# Driver_Filter.net
KiCad netlist of a schematic drawn in Altium Designer
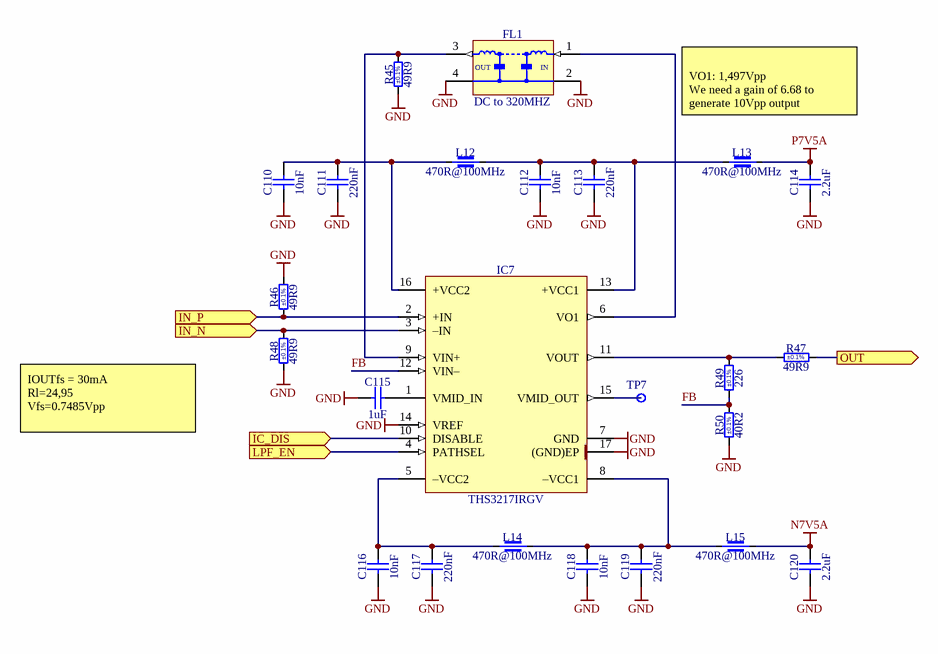
[diagram p0: Driver_Filter.schdoc]

(export (version "E")
  (design (tool "Eeschema 10.0.6"))
  (components
    (comp (ref "C110")
      (value "10nF")
      (footprint "CAPC1005X55N")
      (description "Non-polarised capacitor")
      (fields
        (field (name "PART NUMBER") "CC0402_10NF_16V_10%_X7R")
        (field (name "VOLTAGE") "16V")
        (field (name "AUTHOR") "CERN DEM JLC")
      )
      (libsource (lib "Capacitors") (part "Capacitor - non polarized"))
    )
    (comp (ref "C111")
      (value "220nF")
      (footprint "CAPC1005X55N")
      (description "Non-polarised capacitor")
      (fields
        (field (name "PART NUMBER") "CC0402_220NF_16V_10%_X7R")
        (field (name "VOLTAGE") "16V")
        (field (name "AUTHOR") "CERN DEM JLC")
      )
      (libsource (lib "Capacitors") (part "Capacitor - non polarized"))
    )
    (comp (ref "C112")
      (value "10nF")
      (footprint "CAPC1005X55N")
      (description "Non-polarised capacitor")
      (fields
        (field (name "PART NUMBER") "CC0402_10NF_16V_10%_X7R")
        (field (name "VOLTAGE") "16V")
        (field (name "AUTHOR") "CERN DEM JLC")
      )
      (libsource (lib "Capacitors") (part "Capacitor - non polarized"))
    )
    (comp (ref "C113")
      (value "220nF")
      (footprint "CAPC1005X55N")
      (description "Non-polarised capacitor")
      (fields
        (field (name "PART NUMBER") "CC0402_220NF_16V_10%_X7R")
        (field (name "VOLTAGE") "16V")
        (field (name "AUTHOR") "CERN DEM JLC")
      )
      (libsource (lib "Capacitors") (part "Capacitor - non polarized"))
    )
    (comp (ref "C114")
      (value "2.2uF")
      (footprint "CAPC1005X55N")
      (description "Non-polarised capacitor")
      (fields
        (field (name "PART NUMBER") "CC0402_2.2UF_16V_10%_X5R")
        (field (name "VOLTAGE") "16V")
        (field (name "AUTHOR") "CERN DEM BC")
      )
      (libsource (lib "Capacitors") (part "Capacitor - non polarized"))
    )
    (comp (ref "C115")
      (value "1uF")
      (footprint "CAPC1005X55N")
      (description "Non-polarised capacitor")
      (fields
        (field (name "PART NUMBER") "CC0402_1UF_16V_10%_X5R")
        (field (name "VOLTAGE") "16V")
        (field (name "AUTHOR") "CERN DEM JLC")
      )
      (libsource (lib "Capacitors") (part "Capacitor - non polarized"))
    )
    (comp (ref "C116")
      (value "10nF")
      (footprint "CAPC1005X55N")
      (description "Non-polarised capacitor")
      (fields
        (field (name "PART NUMBER") "CC0402_10NF_16V_10%_X7R")
        (field (name "VOLTAGE") "16V")
        (field (name "AUTHOR") "CERN DEM JLC")
      )
      (libsource (lib "Capacitors") (part "Capacitor - non polarized"))
    )
    (comp (ref "C117")
      (value "220nF")
      (footprint "CAPC1005X55N")
      (description "Non-polarised capacitor")
      (fields
        (field (name "PART NUMBER") "CC0402_220NF_16V_10%_X7R")
        (field (name "VOLTAGE") "16V")
        (field (name "AUTHOR") "CERN DEM JLC")
      )
      (libsource (lib "Capacitors") (part "Capacitor - non polarized"))
    )
    (comp (ref "C118")
      (value "10nF")
      (footprint "CAPC1005X55N")
      (description "Non-polarised capacitor")
      (fields
        (field (name "PART NUMBER") "CC0402_10NF_16V_10%_X7R")
        (field (name "VOLTAGE") "16V")
        (field (name "AUTHOR") "CERN DEM JLC")
      )
      (libsource (lib "Capacitors") (part "Capacitor - non polarized"))
    )
    (comp (ref "C119")
      (value "220nF")
      (footprint "CAPC1005X55N")
      (description "Non-polarised capacitor")
      (fields
        (field (name "PART NUMBER") "CC0402_220NF_16V_10%_X7R")
        (field (name "VOLTAGE") "16V")
        (field (name "AUTHOR") "CERN DEM JLC")
      )
      (libsource (lib "Capacitors") (part "Capacitor - non polarized"))
    )
    (comp (ref "C120")
      (value "2.2uF")
      (footprint "CAPC1005X55N")
      (description "Non-polarised capacitor")
      (fields
        (field (name "PART NUMBER") "CC0402_2.2UF_16V_10%_X5R")
        (field (name "VOLTAGE") "16V")
        (field (name "AUTHOR") "CERN DEM BC")
      )
      (libsource (lib "Capacitors") (part "Capacitor - non polarized"))
    )
    (comp (ref "FL1")
      (value "DC to 320MHZ")
      (footprint "FIL_MINI-CIRCUITS_FV1206")
      (description "50 Ohm Low Pass Filter")
      (fields
        (field (name "PART NUMBER") "FIL_MINI-CIRCUITS_LFCN-320+")
        (field (name "MANUFACTURER") "MINI-CIRCUITS")
        (field (name "AUTHOR") "CERN DEM MR")
      )
      (libsource (lib "Inductors & Transformers") (part "FIL_MINI-CIRCUITS_LFCN"))
    )
    (comp (ref "IC7")
      (value "THS3217IRGV")
      (footprint "QFN65P400X400X100-17N-S225")
      (description "DC to 800-MHz, Differential-to-Single-Ended, DAC Output Amplifier")
      (fields (field (name "MANUFACTURER") "TEXAS INSTRUMENTS") (field (name "AUTHOR") "CERN DEM HF"))
      (libsource (lib "ICs And Semiconductors") (part "THS3217"))
    )
    (comp (ref "L12")
      (value "470R@100MHz")
      (footprint "INDC1608X95N")
      (fields
        (field (name "PART NUMBER") "IND0603_MURATA_BLM18PG471SN1D")
        (field (name "POWER") "1A")
        (field (name "TOLERANCE") "±25%")
        (field (name "AUTHOR") "CERN DEM BC")
      )
      (libsource (lib "Inductors & Transformers") (part "Ferrite Bead"))
    )
    (comp (ref "L13")
      (value "470R@100MHz")
      (footprint "INDC1608X95N")
      (fields
        (field (name "PART NUMBER") "IND0603_MURATA_BLM18PG471SN1D")
        (field (name "POWER") "1A")
        (field (name "TOLERANCE") "±25%")
        (field (name "AUTHOR") "CERN DEM BC")
      )
      (libsource (lib "Inductors & Transformers") (part "Ferrite Bead"))
    )
    (comp (ref "L14")
      (value "470R@100MHz")
      (footprint "INDC1608X95N")
      (fields
        (field (name "PART NUMBER") "IND0603_MURATA_BLM18PG471SN1D")
        (field (name "POWER") "1A")
        (field (name "TOLERANCE") "±25%")
        (field (name "AUTHOR") "CERN DEM BC")
      )
      (libsource (lib "Inductors & Transformers") (part "Ferrite Bead"))
    )
    (comp (ref "L15")
      (value "470R@100MHz")
      (footprint "INDC1608X95N")
      (fields
        (field (name "PART NUMBER") "IND0603_MURATA_BLM18PG471SN1D")
        (field (name "POWER") "1A")
        (field (name "TOLERANCE") "±25%")
        (field (name "AUTHOR") "CERN DEM BC")
      )
      (libsource (lib "Inductors & Transformers") (part "Ferrite Bead"))
    )
    (comp (ref "R45")
      (value "49R9")
      (footprint "RESC1608X55N")
      (description "Resistor - 0.1%")
      (fields
        (field (name "TOLERANCE") "±0.1%")
        (field (name "PART NUMBER") "R0603_49R9_0.1%_0.063W_10PPM")
        (field (name "POWER") "0.063W")
        (field (name "AUTHOR") "CERN DEM JLC")
      )
      (libsource (lib "Resistors") (part "Resistor - 0.1%"))
    )
    (comp (ref "R46")
      (value "49R9")
      (footprint "RESC1608X55N")
      (description "Resistor - 0.1%")
      (fields
        (field (name "TOLERANCE") "±0.1%")
        (field (name "PART NUMBER") "R0603_49R9_0.1%_0.063W_10PPM")
        (field (name "POWER") "0.063W")
        (field (name "AUTHOR") "CERN DEM JLC")
      )
      (libsource (lib "Resistors") (part "Resistor - 0.1%"))
    )
    (comp (ref "R47")
      (value "49R9")
      (footprint "RESC1608X55N")
      (description "Resistor - 0.1%")
      (fields
        (field (name "TOLERANCE") "±0.1%")
        (field (name "PART NUMBER") "R0603_49R9_0.1%_0.063W_10PPM")
        (field (name "POWER") "0.063W")
        (field (name "AUTHOR") "CERN DEM JLC")
      )
      (libsource (lib "Resistors") (part "Resistor - 0.1%"))
    )
    (comp (ref "R48")
      (value "49R9")
      (footprint "RESC1608X55N")
      (description "Resistor - 0.1%")
      (fields
        (field (name "TOLERANCE") "±0.1%")
        (field (name "PART NUMBER") "R0603_49R9_0.1%_0.063W_10PPM")
        (field (name "POWER") "0.063W")
        (field (name "AUTHOR") "CERN DEM JLC")
      )
      (libsource (lib "Resistors") (part "Resistor - 0.1%"))
    )
    (comp (ref "R49")
      (value "226")
      (footprint "RESC1608X55N")
      (description "Resistor - 0.1%")
      (fields
        (field (name "TOLERANCE") "±0.1%")
        (field (name "PART NUMBER") "R0603_226R_0.1%_0.063W_10PPM")
        (field (name "POWER") "0.063W")
        (field (name "AUTHOR") "CERN DEM JLC")
      )
      (libsource (lib "Resistors") (part "Resistor - 0.1%"))
    )
    (comp (ref "R50")
      (value "40R2")
      (footprint "RESC1608X55N")
      (description "Resistor - 0.1%")
      (fields
        (field (name "TOLERANCE") "±0.1%")
        (field (name "PART NUMBER") "R0603_40R2_0.1%_0.063W_10PPM")
        (field (name "POWER") "0.063W")
        (field (name "AUTHOR") "CERN DEM JLC")
      )
      (libsource (lib "Resistors") (part "Resistor - 0.1%"))
    )
    (comp (ref "TP7")
      (value "Test Point")
      (footprint "TPS127")
      (fields (field (name "PART NUMBER") "SMD_PAD_1.27X1.27MM") (field (name "AUTHOR") "CERN DEM JLC"))
      (libsource (lib "Eletro-mechanical") (part "Test Point"))
    )
  )
  (nets
    (net (code "1") (name "/FB") (class "Default")
      (node (ref "IC7") (pin "12") (pinfunction "VIN–_12") (pintype "input"))
      (node (ref "R49") (pin "1") (pinfunction "1_1") (pintype "passive"))
      (node (ref "R50") (pin "2") (pinfunction "2_2") (pintype "passive"))
    )
    (net (code "2") (name "/IC_DIS") (class "Default")
      (node (ref "IC7") (pin "10") (pinfunction "DISABLE_10") (pintype "input"))
    )
    (net (code "3") (name "/IN_N") (class "Default")
      (node (ref "IC7") (pin "3") (pinfunction "–IN_3") (pintype "input"))
      (node (ref "R48") (pin "2") (pinfunction "2_2") (pintype "passive"))
    )
    (net (code "4") (name "/IN_P") (class "Default")
      (node (ref "IC7") (pin "2") (pinfunction "+IN_2") (pintype "input"))
      (node (ref "R46") (pin "1") (pinfunction "1_1") (pintype "passive"))
    )
    (net (code "5") (name "/LPF_EN") (class "Default")
      (node (ref "IC7") (pin "4") (pinfunction "PATHSEL_4") (pintype "input"))
    )
    (net (code "6") (name "/OUT") (class "Default")
      (node (ref "R47") (pin "2") (pinfunction "2_2") (pintype "passive"))
    )
    (net (code "7") (name "GND") (class "Default")
      (node (ref "C110") (pin "1") (pinfunction "1_1") (pintype "passive"))
      (node (ref "C111") (pin "1") (pinfunction "1_1") (pintype "passive"))
      (node (ref "C112") (pin "1") (pinfunction "1_1") (pintype "passive"))
      (node (ref "C113") (pin "1") (pinfunction "1_1") (pintype "passive"))
      (node (ref "C114") (pin "1") (pinfunction "1_1") (pintype "passive"))
      (node (ref "C115") (pin "1") (pinfunction "1_1") (pintype "passive"))
      (node (ref "C116") (pin "1") (pinfunction "1_1") (pintype "passive"))
      (node (ref "C117") (pin "1") (pinfunction "1_1") (pintype "passive"))
      (node (ref "C118") (pin "1") (pinfunction "1_1") (pintype "passive"))
      (node (ref "C119") (pin "1") (pinfunction "1_1") (pintype "passive"))
      (node (ref "C120") (pin "1") (pinfunction "1_1") (pintype "passive"))
      (node (ref "FL1") (pin "2") (pinfunction "GND_2") (pintype "power_in"))
      (node (ref "FL1") (pin "4") (pinfunction "GND_4") (pintype "power_in"))
      (node (ref "IC7") (pin "14") (pinfunction "VREF_14") (pintype "input"))
      (node (ref "IC7") (pin "17") (pinfunction "(GND)EP_17") (pintype "power_in"))
      (node (ref "IC7") (pin "7") (pinfunction "GND_7") (pintype "power_in"))
      (node (ref "R45") (pin "1") (pinfunction "1_1") (pintype "passive"))
      (node (ref "R46") (pin "2") (pinfunction "2_2") (pintype "passive"))
      (node (ref "R48") (pin "1") (pinfunction "1_1") (pintype "passive"))
      (node (ref "R50") (pin "1") (pinfunction "1_1") (pintype "passive"))
    )
    (net (code "8") (name "N7V5A") (class "Default")
      (node (ref "C120") (pin "2") (pinfunction "2_2") (pintype "passive"))
      (node (ref "L15") (pin "2") (pinfunction "2_2") (pintype "passive"))
    )
    (net (code "9") (name "Net-(FL1-RFIN)") (class "Default")
      (node (ref "FL1") (pin "1") (pinfunction "RFIN_1") (pintype "input"))
      (node (ref "IC7") (pin "6") (pinfunction "VO1_6") (pintype "output"))
    )
    (net (code "10") (name "Net-(FL1-RFOUT)") (class "Default")
      (node (ref "FL1") (pin "3") (pinfunction "RFOUT_3") (pintype "output"))
      (node (ref "IC7") (pin "9") (pinfunction "VIN+_9") (pintype "input"))
      (node (ref "R45") (pin "2") (pinfunction "2_2") (pintype "passive"))
    )
    (net (code "11") (name "Net-(IC7-+VCC1)") (class "Default")
      (node (ref "C112") (pin "2") (pinfunction "2_2") (pintype "passive"))
      (node (ref "C113") (pin "2") (pinfunction "2_2") (pintype "passive"))
      (node (ref "IC7") (pin "13") (pinfunction "+VCC1_13") (pintype "power_in"))
      (node (ref "L12") (pin "2") (pinfunction "2_2") (pintype "passive"))
      (node (ref "L13") (pin "1") (pinfunction "1_1") (pintype "passive"))
    )
    (net (code "12") (name "Net-(IC7-+VCC2)") (class "Default")
      (node (ref "C110") (pin "2") (pinfunction "2_2") (pintype "passive"))
      (node (ref "C111") (pin "2") (pinfunction "2_2") (pintype "passive"))
      (node (ref "IC7") (pin "16") (pinfunction "+VCC2_16") (pintype "power_in"))
      (node (ref "L12") (pin "1") (pinfunction "1_1") (pintype "passive"))
    )
    (net (code "13") (name "Net-(IC7-VMID_IN)") (class "Default")
      (node (ref "C115") (pin "2") (pinfunction "2_2") (pintype "passive"))
      (node (ref "IC7") (pin "1") (pinfunction "VMID_IN_1") (pintype "power_in"))
    )
    (net (code "14") (name "Net-(IC7-VMID_OUT)") (class "Default")
      (node (ref "IC7") (pin "15") (pinfunction "VMID_OUT_15") (pintype "output"))
      (node (ref "TP7") (pin "1") (pinfunction "1_1") (pintype "bidirectional"))
    )
    (net (code "15") (name "Net-(IC7-VOUT)") (class "Default")
      (node (ref "IC7") (pin "11") (pinfunction "VOUT_11") (pintype "output"))
      (node (ref "R47") (pin "1") (pinfunction "1_1") (pintype "passive"))
      (node (ref "R49") (pin "2") (pinfunction "2_2") (pintype "passive"))
    )
    (net (code "16") (name "Net-(IC7-–VCC1)") (class "Default")
      (node (ref "C118") (pin "2") (pinfunction "2_2") (pintype "passive"))
      (node (ref "C119") (pin "2") (pinfunction "2_2") (pintype "passive"))
      (node (ref "IC7") (pin "8") (pinfunction "–VCC1_8") (pintype "power_in"))
      (node (ref "L14") (pin "2") (pinfunction "2_2") (pintype "passive"))
      (node (ref "L15") (pin "1") (pinfunction "1_1") (pintype "passive"))
    )
    (net (code "17") (name "Net-(IC7-–VCC2)") (class "Default")
      (node (ref "C116") (pin "2") (pinfunction "2_2") (pintype "passive"))
      (node (ref "C117") (pin "2") (pinfunction "2_2") (pintype "passive"))
      (node (ref "IC7") (pin "5") (pinfunction "–VCC2_5") (pintype "power_in"))
      (node (ref "L14") (pin "1") (pinfunction "1_1") (pintype "passive"))
    )
    (net (code "18") (name "P7V5A") (class "Default")
      (node (ref "C114") (pin "2") (pinfunction "2_2") (pintype "passive"))
      (node (ref "L13") (pin "2") (pinfunction "2_2") (pintype "passive"))
    )
  )
)
